# 12v_converter.net
KiCad netlist of a schematic drawn in EAGLE
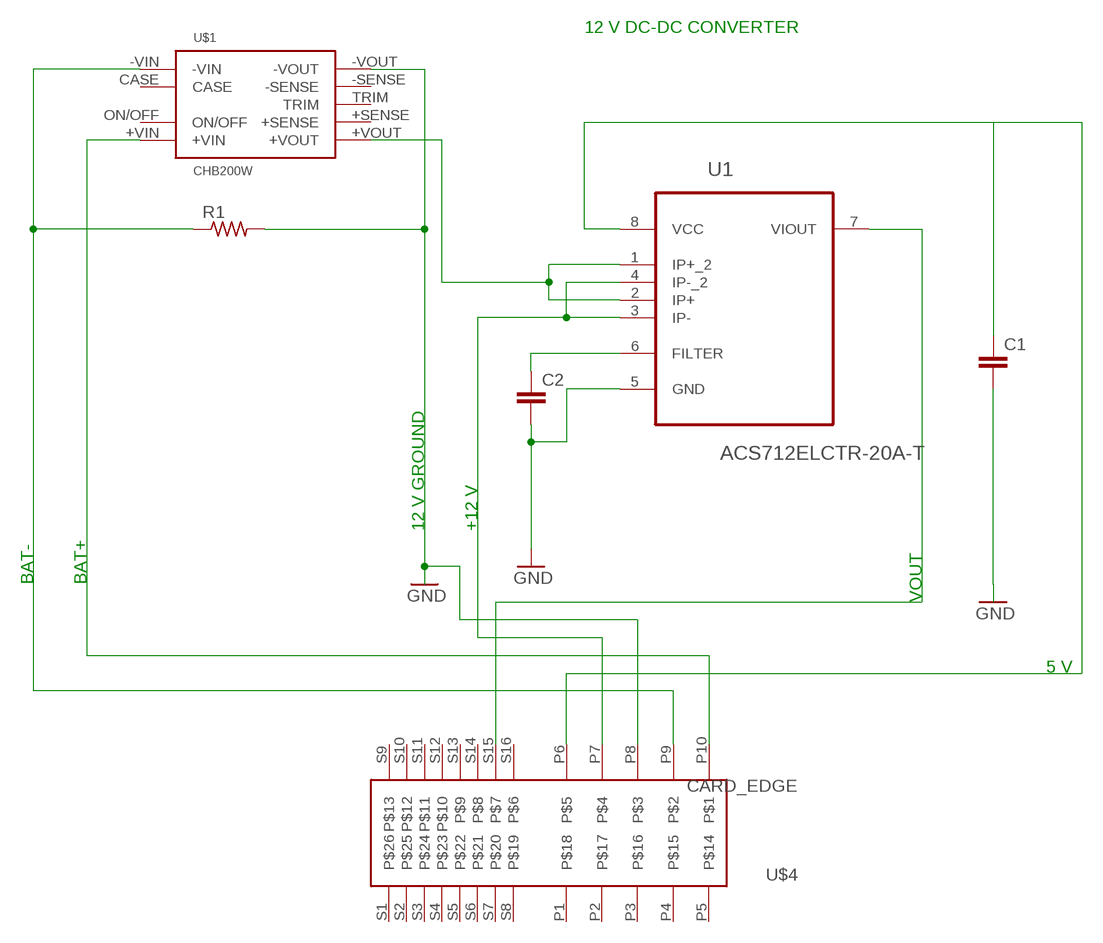
[diagram p0: schematic, sheet 1]

(export (version "E")
  (design (tool "Eeschema 10.0.6"))
  (components
    (comp (ref "C1")
      (value "C-EU025-024X044")
      (footprint "eagle-import:C025-024X044")
      (libsource (lib "eagle-import") (part "C-EU025-024X044"))
    )
    (comp (ref "C2")
      (value "C-EU025-024X044")
      (footprint "eagle-import:C025-024X044")
      (libsource (lib "eagle-import") (part "C-EU025-024X044"))
    )
    (comp (ref "R1")
      (value "R-US_0204/2V")
      (footprint "eagle-import:0204V")
      (libsource (lib "eagle-import") (part "R-US_0204/2V"))
    )
    (comp (ref "U$1")
      (value "CHB200W")
      (footprint "eagle-import:CHB200W-24S12")
      (libsource (lib "eagle-import") (part "CHB200W"))
    )
    (comp (ref "U$4")
      (value "CARD_EDGE")
      (footprint "eagle-import:EDGE_CONNECTOR")
      (libsource (lib "eagle-import") (part "CARD_EDGE"))
    )
    (comp (ref "U1")
      (value "ACS712ELCTR-20A-T")
      (footprint "eagle-import:SOIC127P600X175-8N")
      (libsource (lib "eagle-import") (part "ACS712ELCTR-20A-T"))
    )
  )
  (nets
    (net (code "1") (name "GND") (class "Default")
      (node (ref "C1") (pin "2") (pinfunction "2_2") (pintype "passive"))
      (node (ref "C2") (pin "2") (pinfunction "2_2") (pintype "passive"))
      (node (ref "R1") (pin "2") (pinfunction "2_2") (pintype "passive"))
      (node (ref "U$1") (pin "-VOUT") (pinfunction "-VOUT_-VOUT") (pintype "bidirectional"))
      (node (ref "U$4") (pin "P8") (pinfunction "P$3_P8") (pintype "bidirectional"))
      (node (ref "U1") (pin "5") (pinfunction "GND_5") (pintype "passive"))
    )
    (net (code "2") (name "Net-(U$4-P$1)") (class "Default")
      (node (ref "U$1") (pin "+VIN") (pinfunction "+VIN_+VIN") (pintype "bidirectional"))
      (node (ref "U$4") (pin "P10") (pinfunction "P$1_P10") (pintype "bidirectional"))
    )
    (net (code "3") (name "Net-(U$4-P$2)") (class "Default")
      (node (ref "R1") (pin "1") (pinfunction "1_1") (pintype "passive"))
      (node (ref "U$1") (pin "-VIN") (pinfunction "-VIN_-VIN") (pintype "bidirectional"))
      (node (ref "U$4") (pin "P9") (pinfunction "P$2_P9") (pintype "bidirectional"))
    )
    (net (code "4") (name "Net-(U$4-P$4)") (class "Default")
      (node (ref "U$4") (pin "P7") (pinfunction "P$4_P7") (pintype "bidirectional"))
      (node (ref "U1") (pin "3") (pinfunction "IP-_3") (pintype "input"))
      (node (ref "U1") (pin "4") (pinfunction "IP-_2_4") (pintype "input"))
    )
    (net (code "5") (name "Net-(U$4-P$5)") (class "Default")
      (node (ref "C1") (pin "1") (pinfunction "1_1") (pintype "passive"))
      (node (ref "U$4") (pin "P6") (pinfunction "P$5_P6") (pintype "bidirectional"))
      (node (ref "U1") (pin "8") (pinfunction "VCC_8") (pintype "power_in"))
    )
    (net (code "6") (name "Net-(U$4-P$7)") (class "Default")
      (node (ref "U$4") (pin "S15") (pinfunction "P$7_S15") (pintype "bidirectional"))
      (node (ref "U1") (pin "7") (pinfunction "VIOUT_7") (pintype "output"))
    )
    (net (code "7") (name "Net-(U1-FILTER)") (class "Default")
      (node (ref "C2") (pin "1") (pinfunction "1_1") (pintype "passive"))
      (node (ref "U1") (pin "6") (pinfunction "FILTER_6") (pintype "input"))
    )
    (net (code "8") (name "Net-(U1-IP+)") (class "Default")
      (node (ref "U$1") (pin "+VOUT") (pinfunction "+VOUT_+VOUT") (pintype "bidirectional"))
      (node (ref "U1") (pin "1") (pinfunction "IP+_2_1") (pintype "input"))
      (node (ref "U1") (pin "2") (pinfunction "IP+_2") (pintype "input"))
    )
    (net (code "9") (name "unconnected-(U$1-Pad+SENSE)") (class "Default")
      (node (ref "U$1") (pin "+SENSE") (pinfunction "+SENSE_+SENSE") (pintype "bidirectional"))
    )
    (net (code "10") (name "unconnected-(U$1-Pad-SENSE)") (class "Default")
      (node (ref "U$1") (pin "-SENSE") (pinfunction "-SENSE_-SENSE") (pintype "bidirectional"))
    )
    (net (code "11") (name "unconnected-(U$1-PadCASE)") (class "Default")
      (node (ref "U$1") (pin "CASE") (pinfunction "CASE_CASE") (pintype "bidirectional"))
    )
    (net (code "12") (name "unconnected-(U$1-PadON{slash}OFF)") (class "Default")
      (node (ref "U$1") (pin "ON/OFF") (pinfunction "ON/OFF_ON/OFF") (pintype "bidirectional"))
    )
    (net (code "13") (name "unconnected-(U$1-PadTRIM)") (class "Default")
      (node (ref "U$1") (pin "TRIM") (pinfunction "TRIM_TRIM") (pintype "bidirectional"))
    )
    (net (code "14") (name "unconnected-(U$4-P$6-PadS16)") (class "Default")
      (node (ref "U$4") (pin "S16") (pinfunction "P$6_S16") (pintype "bidirectional"))
    )
    (net (code "15") (name "unconnected-(U$4-P$8-PadS14)") (class "Default")
      (node (ref "U$4") (pin "S14") (pinfunction "P$8_S14") (pintype "bidirectional"))
    )
    (net (code "16") (name "unconnected-(U$4-P$9-PadS13)") (class "Default")
      (node (ref "U$4") (pin "S13") (pinfunction "P$9_S13") (pintype "bidirectional"))
    )
    (net (code "17") (name "unconnected-(U$4-P$10-PadS12)") (class "Default")
      (node (ref "U$4") (pin "S12") (pinfunction "P$10_S12") (pintype "bidirectional"))
    )
    (net (code "18") (name "unconnected-(U$4-P$11-PadS11)") (class "Default")
      (node (ref "U$4") (pin "S11") (pinfunction "P$11_S11") (pintype "bidirectional"))
    )
    (net (code "19") (name "unconnected-(U$4-P$12-PadS10)") (class "Default")
      (node (ref "U$4") (pin "S10") (pinfunction "P$12_S10") (pintype "bidirectional"))
    )
    (net (code "20") (name "unconnected-(U$4-P$13-PadS9)") (class "Default")
      (node (ref "U$4") (pin "S9") (pinfunction "P$13_S9") (pintype "bidirectional"))
    )
    (net (code "21") (name "unconnected-(U$4-P$14-PadP5)") (class "Default")
      (node (ref "U$4") (pin "P5") (pinfunction "P$14_P5") (pintype "bidirectional"))
    )
    (net (code "22") (name "unconnected-(U$4-P$15-PadP4)") (class "Default")
      (node (ref "U$4") (pin "P4") (pinfunction "P$15_P4") (pintype "bidirectional"))
    )
    (net (code "23") (name "unconnected-(U$4-P$16-PadP3)") (class "Default")
      (node (ref "U$4") (pin "P3") (pinfunction "P$16_P3") (pintype "bidirectional"))
    )
    (net (code "24") (name "unconnected-(U$4-P$17-PadP2)") (class "Default")
      (node (ref "U$4") (pin "P2") (pinfunction "P$17_P2") (pintype "bidirectional"))
    )
    (net (code "25") (name "unconnected-(U$4-P$18-PadP1)") (class "Default")
      (node (ref "U$4") (pin "P1") (pinfunction "P$18_P1") (pintype "bidirectional"))
    )
    (net (code "26") (name "unconnected-(U$4-P$19-PadS8)") (class "Default")
      (node (ref "U$4") (pin "S8") (pinfunction "P$19_S8") (pintype "bidirectional"))
    )
    (net (code "27") (name "unconnected-(U$4-P$20-PadS7)") (class "Default")
      (node (ref "U$4") (pin "S7") (pinfunction "P$20_S7") (pintype "bidirectional"))
    )
    (net (code "28") (name "unconnected-(U$4-P$21-PadS6)") (class "Default")
      (node (ref "U$4") (pin "S6") (pinfunction "P$21_S6") (pintype "bidirectional"))
    )
    (net (code "29") (name "unconnected-(U$4-P$22-PadS5)") (class "Default")
      (node (ref "U$4") (pin "S5") (pinfunction "P$22_S5") (pintype "bidirectional"))
    )
    (net (code "30") (name "unconnected-(U$4-P$23-PadS4)") (class "Default")
      (node (ref "U$4") (pin "S4") (pinfunction "P$23_S4") (pintype "bidirectional"))
    )
    (net (code "31") (name "unconnected-(U$4-P$24-PadS3)") (class "Default")
      (node (ref "U$4") (pin "S3") (pinfunction "P$24_S3") (pintype "bidirectional"))
    )
    (net (code "32") (name "unconnected-(U$4-P$25-PadS2)") (class "Default")
      (node (ref "U$4") (pin "S2") (pinfunction "P$25_S2") (pintype "bidirectional"))
    )
    (net (code "33") (name "unconnected-(U$4-P$26-PadS1)") (class "Default")
      (node (ref "U$4") (pin "S1") (pinfunction "P$26_S1") (pintype "bidirectional"))
    )
  )
)
